# RPI_CM5_PINOUT.net
KiCad netlist of a schematic drawn in Altium Designer
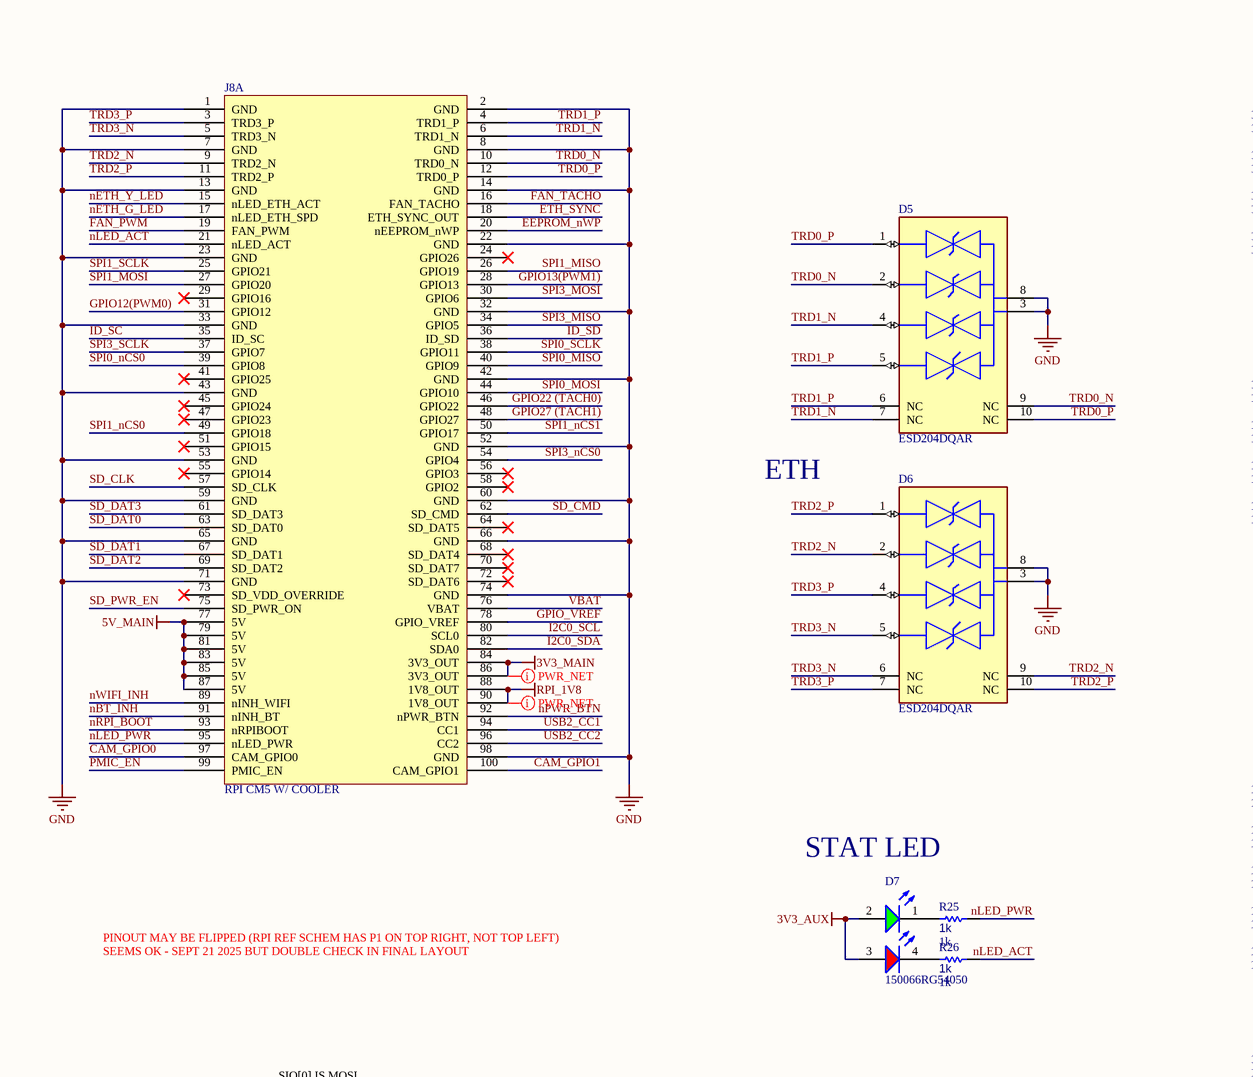
[diagram p0: RPI_CM5_PINOUT.SchDoc, top left]
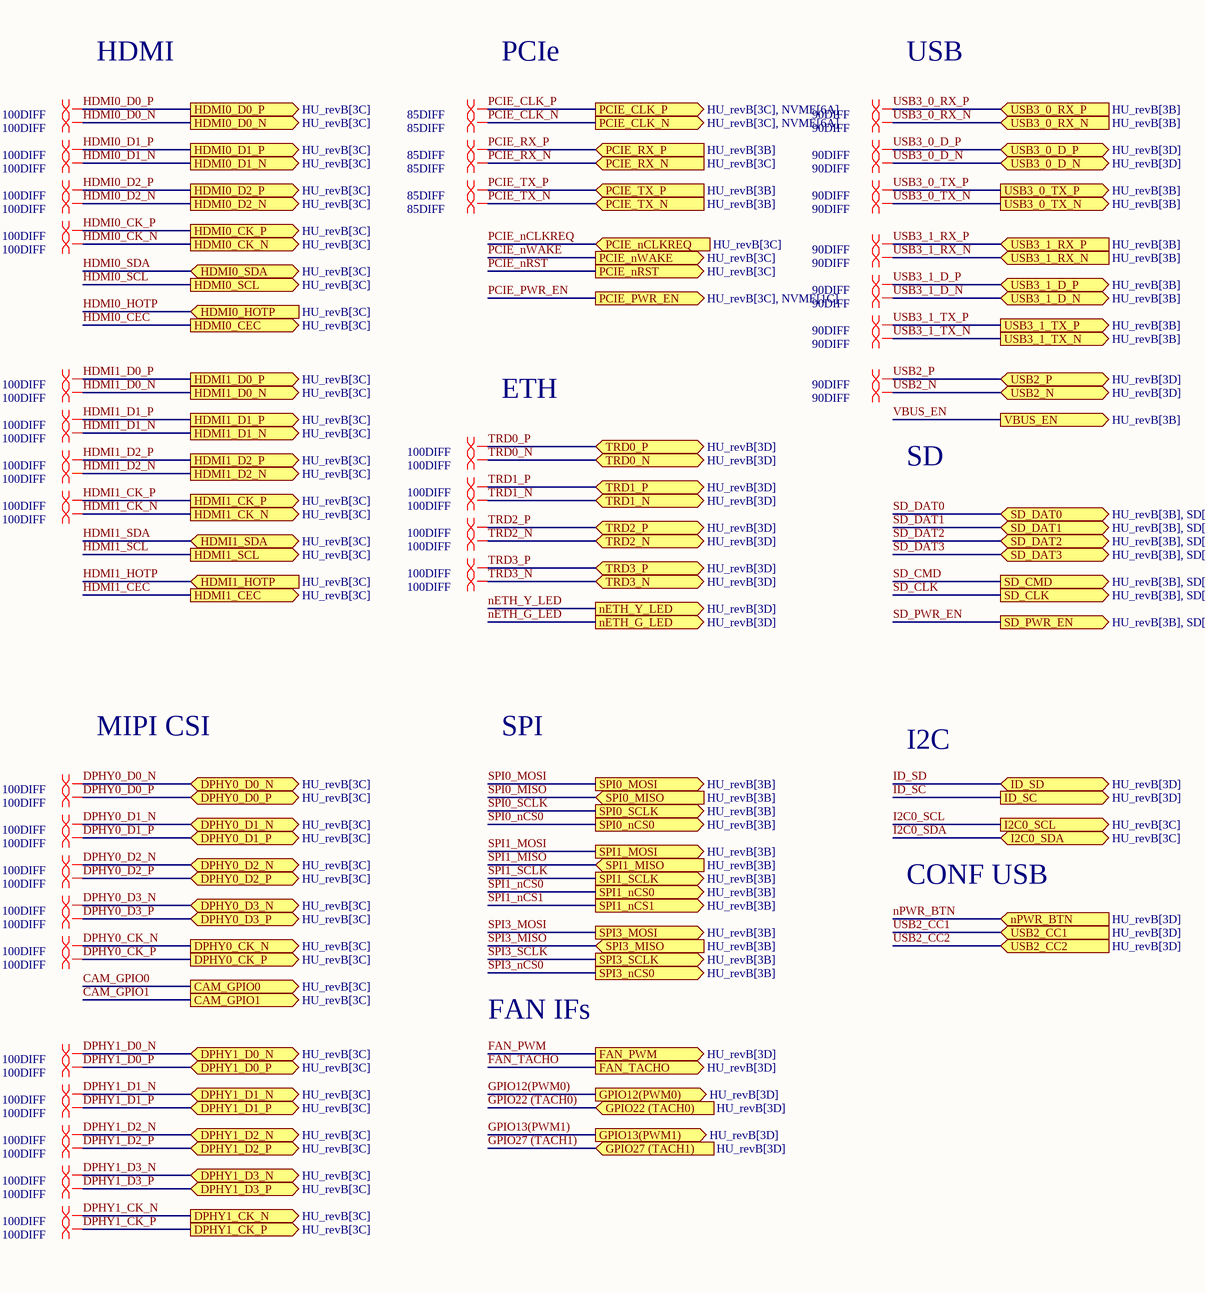
[diagram p1: RPI_CM5_PINOUT.SchDoc, top right]
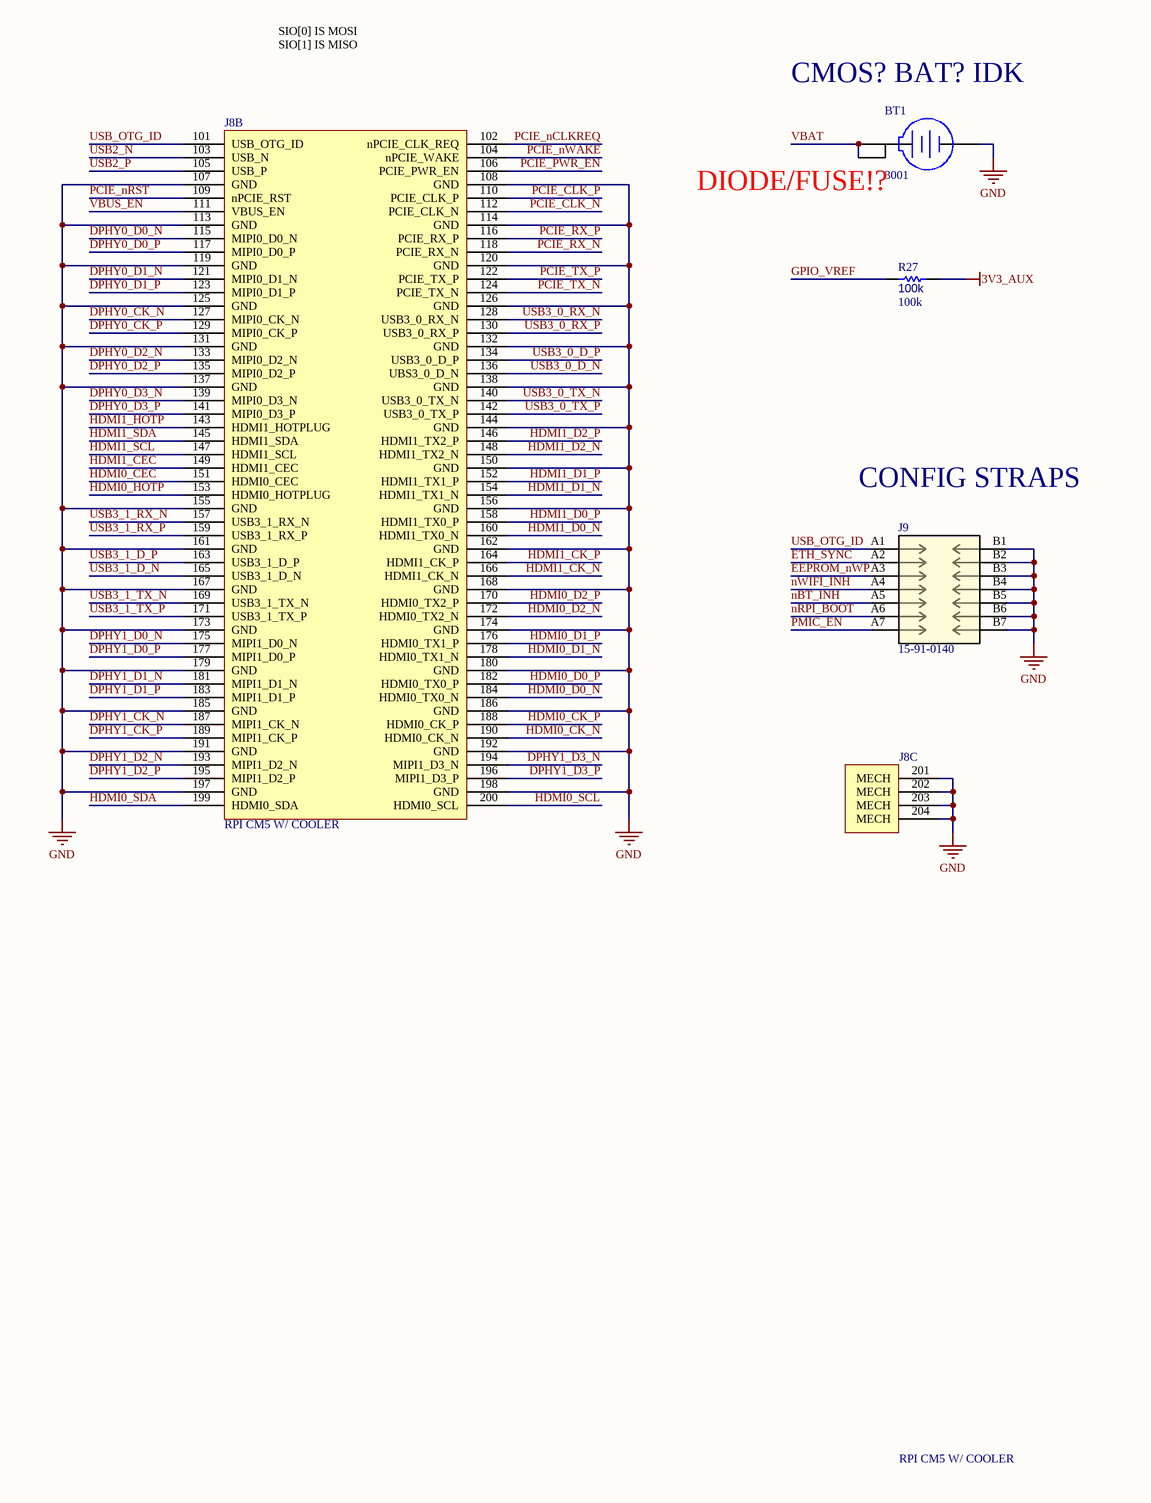
[diagram p2: RPI_CM5_PINOUT.SchDoc, bottom left]
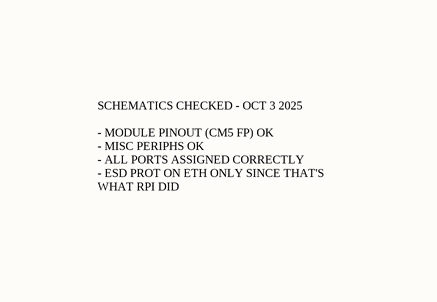
[diagram p3: RPI_CM5_PINOUT.SchDoc, bottom right]

(export (version "E")
  (design (tool "Eeschema 10.0.6"))
  (components
    (comp (ref "BT1")
      (value "3001")
      (footprint "KSTN-3001_V")
      (description "Holder Battery Coin, 12 mm, 2-Pin THD, RoHS")
      (fields (field (name "MANUFACTURER") "Keystone"))
      (libsource (lib "Altium Content Vault") (part "BATTERY-HOLDER-COIN-3"))
    )
    (comp (ref "D5")
      (value "ESD204DQAR")
      (footprint "FP-DQA0010A-MFG")
      (description "4-CHANNEL LOW-CAPACITANCE SURGE")
      (fields
        (field (name "MANUFACTURER") "Texas Instruments")
        (field (name "OCTOPART") "https://octopart.com/esd204dqar-texas+instruments-89917476")
      )
      (libsource (lib "Altium Content Vault") (part "1465e58c1818c7767b55926832f0bf5"))
    )
    (comp (ref "D6")
      (value "ESD204DQAR")
      (footprint "FP-DQA0010A-MFG")
      (description "4-CHANNEL LOW-CAPACITANCE SURGE")
      (fields
        (field (name "MANUFACTURER") "Texas Instruments")
        (field (name "OCTOPART") "https://octopart.com/esd204dqar-texas+instruments-89917476")
      )
      (libsource (lib "Altium Content Vault") (part "1465e58c1818c7767b55926832f0bf5"))
    )
    (comp (ref "D7")
      (value "150066RG54050")
      (footprint "WL-SBCD_0606")
      (description "Led, Red/Grn, 180Mcd/230Mcd, 624Nm/525Nm Rohs Compliant: Yes")
      (fields (field (name "SOURCE") "rgled.SchLib"))
      (libsource (lib "Space Concordia") (part "CMP-004-00034-2"))
    )
    (comp (ref "J8")
      (value "RPI CM5 W/ COOLER")
      (footprint "RPI CM5 W_ COOLER-Footprint-1")
      (description "Mechanical placeholder for RPI CM5 w/ active cooler on it")
      (libsource (lib "Space Concordia") (part "10164227-1001A1RLF"))
    )
    (comp (ref "J9")
      (value "15-91-0140")
      (footprint "15-91-0140-Footprint-1")
      (description "Conn.; Rect./PCB; Header; 14 Circuit; SMT; Dual Row; Vertical; C-Grid Series; Gold Plate")
      (libsource (lib "Space Concordia") (part "15-91-0140"))
    )
    (comp (ref "R25")
      (value "1k")
      (footprint "R0603B")
      (description "Resistor")
      (fields (field (name "ALTIUM_VALUE") "1k"))
      (libsource (lib "Space Concordia") (part "Resistor"))
    )
    (comp (ref "R26")
      (value "1k")
      (footprint "R0603B")
      (description "Resistor")
      (fields (field (name "ALTIUM_VALUE") "1k"))
      (libsource (lib "Space Concordia") (part "Resistor"))
    )
    (comp (ref "R27")
      (value "100k")
      (footprint "R0603B")
      (description "Resistor")
      (fields (field (name "ALTIUM_VALUE") "100k"))
      (libsource (lib "Space Concordia") (part "Resistor"))
    )
  )
  (nets
    (net (code "1") (name "/CAM_GPIO0") (class "Default")
      (node (ref "J8") (pin "97") (pinfunction "CAM_GPIO0_97") (pintype "passive"))
    )
    (net (code "2") (name "/CAM_GPIO1") (class "Default")
      (node (ref "J8") (pin "100") (pinfunction "CAM_GPIO1_100") (pintype "passive"))
    )
    (net (code "3") (name "/DPHY0_CK_N") (class "Default")
      (node (ref "J8") (pin "127") (pinfunction "MIPI0_CK_N_127") (pintype "passive"))
    )
    (net (code "4") (name "/DPHY0_CK_P") (class "Default")
      (node (ref "J8") (pin "129") (pinfunction "MIPI0_CK_P_129") (pintype "passive"))
    )
    (net (code "5") (name "/DPHY0_D0_N") (class "Default")
      (node (ref "J8") (pin "115") (pinfunction "MIPI0_D0_N_115") (pintype "passive"))
    )
    (net (code "6") (name "/DPHY0_D0_P") (class "Default")
      (node (ref "J8") (pin "117") (pinfunction "MIPI0_D0_P_117") (pintype "passive"))
    )
    (net (code "7") (name "/DPHY0_D1_N") (class "Default")
      (node (ref "J8") (pin "121") (pinfunction "MIPI0_D1_N_121") (pintype "passive"))
    )
    (net (code "8") (name "/DPHY0_D1_P") (class "Default")
      (node (ref "J8") (pin "123") (pinfunction "MIPI0_D1_P_123") (pintype "passive"))
    )
    (net (code "9") (name "/DPHY0_D2_N") (class "Default")
      (node (ref "J8") (pin "133") (pinfunction "MIPI0_D2_N_133") (pintype "passive"))
    )
    (net (code "10") (name "/DPHY0_D2_P") (class "Default")
      (node (ref "J8") (pin "135") (pinfunction "MIPI0_D2_P_135") (pintype "passive"))
    )
    (net (code "11") (name "/DPHY0_D3_N") (class "Default")
      (node (ref "J8") (pin "139") (pinfunction "MIPI0_D3_N_139") (pintype "passive"))
    )
    (net (code "12") (name "/DPHY0_D3_P") (class "Default")
      (node (ref "J8") (pin "141") (pinfunction "MIPI0_D3_P_141") (pintype "passive"))
    )
    (net (code "13") (name "/DPHY1_CK_N") (class "Default")
      (node (ref "J8") (pin "187") (pinfunction "MIPI1_CK_N_187") (pintype "passive"))
    )
    (net (code "14") (name "/DPHY1_CK_P") (class "Default")
      (node (ref "J8") (pin "189") (pinfunction "MIPI1_CK_P_189") (pintype "passive"))
    )
    (net (code "15") (name "/DPHY1_D0_N") (class "Default")
      (node (ref "J8") (pin "175") (pinfunction "MIPI1_D0_N_175") (pintype "passive"))
    )
    (net (code "16") (name "/DPHY1_D0_P") (class "Default")
      (node (ref "J8") (pin "177") (pinfunction "MIPI1_D0_P_177") (pintype "passive"))
    )
    (net (code "17") (name "/DPHY1_D1_N") (class "Default")
      (node (ref "J8") (pin "181") (pinfunction "MIPI1_D1_N_181") (pintype "passive"))
    )
    (net (code "18") (name "/DPHY1_D1_P") (class "Default")
      (node (ref "J8") (pin "183") (pinfunction "MIPI1_D1_P_183") (pintype "passive"))
    )
    (net (code "19") (name "/DPHY1_D2_N") (class "Default")
      (node (ref "J8") (pin "193") (pinfunction "MIPI1_D2_N_193") (pintype "passive"))
    )
    (net (code "20") (name "/DPHY1_D2_P") (class "Default")
      (node (ref "J8") (pin "195") (pinfunction "MIPI1_D2_P_195") (pintype "passive"))
    )
    (net (code "21") (name "/DPHY1_D3_N") (class "Default")
      (node (ref "J8") (pin "194") (pinfunction "MIPI1_D3_N_194") (pintype "passive"))
    )
    (net (code "22") (name "/DPHY1_D3_P") (class "Default")
      (node (ref "J8") (pin "196") (pinfunction "MIPI1_D3_P_196") (pintype "passive"))
    )
    (net (code "23") (name "/EEPROM_nWP") (class "Default")
      (node (ref "J8") (pin "20") (pinfunction "nEEPROM_nWP_20") (pintype "passive"))
      (node (ref "J9") (pin "A3") (pinfunction "A3_A3") (pintype "passive"))
    )
    (net (code "24") (name "/ETH_SYNC") (class "Default")
      (node (ref "J8") (pin "18") (pinfunction "ETH_SYNC_OUT_18") (pintype "passive"))
      (node (ref "J9") (pin "A2") (pinfunction "A2_A2") (pintype "passive"))
    )
    (net (code "25") (name "/FAN_PWM") (class "Default")
      (node (ref "J8") (pin "19") (pinfunction "FAN_PWM_19") (pintype "passive"))
    )
    (net (code "26") (name "/FAN_TACHO") (class "Default")
      (node (ref "J8") (pin "16") (pinfunction "FAN_TACHO_16") (pintype "passive"))
    )
    (net (code "27") (name "/GPIO12(PWM0)") (class "Default")
      (node (ref "J8") (pin "31") (pinfunction "GPIO12_31") (pintype "passive"))
    )
    (net (code "28") (name "/GPIO13(PWM1)") (class "Default")
      (node (ref "J8") (pin "28") (pinfunction "GPIO13_28") (pintype "passive"))
    )
    (net (code "29") (name "/GPIO22 (TACH0)") (class "Default")
      (node (ref "J8") (pin "46") (pinfunction "GPIO22_46") (pintype "passive"))
    )
    (net (code "30") (name "/GPIO27 (TACH1)") (class "Default")
      (node (ref "J8") (pin "48") (pinfunction "GPIO27_48") (pintype "passive"))
    )
    (net (code "31") (name "/GPIO_VREF") (class "Default")
      (node (ref "J8") (pin "78") (pinfunction "GPIO_VREF_78") (pintype "passive"))
      (node (ref "R27") (pin "1") (pinfunction "1_1") (pintype "passive"))
    )
    (net (code "32") (name "/HDMI0_CEC") (class "Default")
      (node (ref "J8") (pin "151") (pinfunction "HDMI0_CEC_151") (pintype "passive"))
    )
    (net (code "33") (name "/HDMI0_CK_N") (class "Default")
      (node (ref "J8") (pin "190") (pinfunction "HDMI0_CK_N_190") (pintype "passive"))
    )
    (net (code "34") (name "/HDMI0_CK_P") (class "Default")
      (node (ref "J8") (pin "188") (pinfunction "HDMI0_CK_P_188") (pintype "passive"))
    )
    (net (code "35") (name "/HDMI0_D0_N") (class "Default")
      (node (ref "J8") (pin "184") (pinfunction "HDMI0_TX0_N_184") (pintype "passive"))
    )
    (net (code "36") (name "/HDMI0_D0_P") (class "Default")
      (node (ref "J8") (pin "182") (pinfunction "HDMI0_TX0_P_182") (pintype "passive"))
    )
    (net (code "37") (name "/HDMI0_D1_N") (class "Default")
      (node (ref "J8") (pin "178") (pinfunction "HDMI0_TX1_N_178") (pintype "passive"))
    )
    (net (code "38") (name "/HDMI0_D1_P") (class "Default")
      (node (ref "J8") (pin "176") (pinfunction "HDMI0_TX1_P_176") (pintype "passive"))
    )
    (net (code "39") (name "/HDMI0_D2_N") (class "Default")
      (node (ref "J8") (pin "172") (pinfunction "HDMI0_TX2_N_172") (pintype "passive"))
    )
    (net (code "40") (name "/HDMI0_D2_P") (class "Default")
      (node (ref "J8") (pin "170") (pinfunction "HDMI0_TX2_P_170") (pintype "passive"))
    )
    (net (code "41") (name "/HDMI0_HOTP") (class "Default")
      (node (ref "J8") (pin "153") (pinfunction "HDMI0_HOTPLUG_153") (pintype "passive"))
    )
    (net (code "42") (name "/HDMI0_SCL") (class "Default")
      (node (ref "J8") (pin "200") (pinfunction "HDMI0_SCL_200") (pintype "passive"))
    )
    (net (code "43") (name "/HDMI0_SDA") (class "Default")
      (node (ref "J8") (pin "199") (pinfunction "HDMI0_SDA_199") (pintype "passive"))
    )
    (net (code "44") (name "/HDMI1_CEC") (class "Default")
      (node (ref "J8") (pin "149") (pinfunction "HDMI1_CEC_149") (pintype "passive"))
    )
    (net (code "45") (name "/HDMI1_CK_N") (class "Default")
      (node (ref "J8") (pin "166") (pinfunction "HDMI1_CK_N_166") (pintype "passive"))
    )
    (net (code "46") (name "/HDMI1_CK_P") (class "Default")
      (node (ref "J8") (pin "164") (pinfunction "HDMI1_CK_P_164") (pintype "passive"))
    )
    (net (code "47") (name "/HDMI1_D0_N") (class "Default")
      (node (ref "J8") (pin "160") (pinfunction "HDMI1_TX0_N_160") (pintype "passive"))
    )
    (net (code "48") (name "/HDMI1_D0_P") (class "Default")
      (node (ref "J8") (pin "158") (pinfunction "HDMI1_TX0_P_158") (pintype "passive"))
    )
    (net (code "49") (name "/HDMI1_D1_N") (class "Default")
      (node (ref "J8") (pin "154") (pinfunction "HDMI1_TX1_N_154") (pintype "passive"))
    )
    (net (code "50") (name "/HDMI1_D1_P") (class "Default")
      (node (ref "J8") (pin "152") (pinfunction "HDMI1_TX1_P_152") (pintype "passive"))
    )
    (net (code "51") (name "/HDMI1_D2_N") (class "Default")
      (node (ref "J8") (pin "148") (pinfunction "HDMI1_TX2_N_148") (pintype "passive"))
    )
    (net (code "52") (name "/HDMI1_D2_P") (class "Default")
      (node (ref "J8") (pin "146") (pinfunction "HDMI1_TX2_P_146") (pintype "passive"))
    )
    (net (code "53") (name "/HDMI1_HOTP") (class "Default")
      (node (ref "J8") (pin "143") (pinfunction "HDMI1_HOTPLUG_143") (pintype "passive"))
    )
    (net (code "54") (name "/HDMI1_SCL") (class "Default")
      (node (ref "J8") (pin "147") (pinfunction "HDMI1_SCL_147") (pintype "passive"))
    )
    (net (code "55") (name "/HDMI1_SDA") (class "Default")
      (node (ref "J8") (pin "145") (pinfunction "HDMI1_SDA_145") (pintype "passive"))
    )
    (net (code "56") (name "/I2C0_SCL") (class "Default")
      (node (ref "J8") (pin "80") (pinfunction "SCL0_80") (pintype "passive"))
    )
    (net (code "57") (name "/I2C0_SDA") (class "Default")
      (node (ref "J8") (pin "82") (pinfunction "SDA0_82") (pintype "passive"))
    )
    (net (code "58") (name "/ID_SC") (class "Default")
      (node (ref "J8") (pin "35") (pinfunction "ID_SC_35") (pintype "passive"))
    )
    (net (code "59") (name "/ID_SD") (class "Default")
      (node (ref "J8") (pin "36") (pinfunction "ID_SD_36") (pintype "passive"))
    )
    (net (code "60") (name "/PCIE_CLK_N") (class "Default")
      (node (ref "J8") (pin "112") (pinfunction "PCIE_CLK_N_112") (pintype "passive"))
    )
    (net (code "61") (name "/PCIE_CLK_P") (class "Default")
      (node (ref "J8") (pin "110") (pinfunction "PCIE_CLK_P_110") (pintype "passive"))
    )
    (net (code "62") (name "/PCIE_PWR_EN") (class "Default")
      (node (ref "J8") (pin "106") (pinfunction "PCIE_PWR_EN_106") (pintype "passive"))
    )
    (net (code "63") (name "/PCIE_RX_N") (class "Default")
      (node (ref "J8") (pin "118") (pinfunction "PCIE_RX_N_118") (pintype "passive"))
    )
    (net (code "64") (name "/PCIE_RX_P") (class "Default")
      (node (ref "J8") (pin "116") (pinfunction "PCIE_RX_P_116") (pintype "passive"))
    )
    (net (code "65") (name "/PCIE_TX_N") (class "Default")
      (node (ref "J8") (pin "124") (pinfunction "PCIE_TX_N_124") (pintype "passive"))
    )
    (net (code "66") (name "/PCIE_TX_P") (class "Default")
      (node (ref "J8") (pin "122") (pinfunction "PCIE_TX_P_122") (pintype "passive"))
    )
    (net (code "67") (name "/PCIE_nCLKREQ") (class "Default")
      (node (ref "J8") (pin "102") (pinfunction "nPCIE_CLK_REQ_102") (pintype "passive"))
    )
    (net (code "68") (name "/PCIE_nRST") (class "Default")
      (node (ref "J8") (pin "109") (pinfunction "nPCIE_RST_109") (pintype "passive"))
    )
    (net (code "69") (name "/PCIE_nWAKE") (class "Default")
      (node (ref "J8") (pin "104") (pinfunction "nPCIE_WAKE_104") (pintype "passive"))
    )
    (net (code "70") (name "/PMIC_EN") (class "Default")
      (node (ref "J8") (pin "99") (pinfunction "PMIC_EN_99") (pintype "passive"))
      (node (ref "J9") (pin "A7") (pinfunction "A7_A7") (pintype "passive"))
    )
    (net (code "71") (name "/SD_CLK") (class "Default")
      (node (ref "J8") (pin "57") (pinfunction "SD_CLK_57") (pintype "passive"))
    )
    (net (code "72") (name "/SD_CMD") (class "Default")
      (node (ref "J8") (pin "62") (pinfunction "SD_CMD_62") (pintype "passive"))
    )
    (net (code "73") (name "/SD_DAT0") (class "Default")
      (node (ref "J8") (pin "63") (pinfunction "SD_DAT0_63") (pintype "passive"))
    )
    (net (code "74") (name "/SD_DAT1") (class "Default")
      (node (ref "J8") (pin "67") (pinfunction "SD_DAT1_67") (pintype "passive"))
    )
    (net (code "75") (name "/SD_DAT2") (class "Default")
      (node (ref "J8") (pin "69") (pinfunction "SD_DAT2_69") (pintype "passive"))
    )
    (net (code "76") (name "/SD_DAT3") (class "Default")
      (node (ref "J8") (pin "61") (pinfunction "SD_DAT3_61") (pintype "passive"))
    )
    (net (code "77") (name "/SD_PWR_EN") (class "Default")
      (node (ref "J8") (pin "75") (pinfunction "SD_PWR_ON_75") (pintype "passive"))
    )
    (net (code "78") (name "/SPI0_MISO") (class "Default")
      (node (ref "J8") (pin "40") (pinfunction "GPIO9_40") (pintype "passive"))
    )
    (net (code "79") (name "/SPI0_MOSI") (class "Default")
      (node (ref "J8") (pin "44") (pinfunction "GPIO10_44") (pintype "passive"))
    )
    (net (code "80") (name "/SPI0_SCLK") (class "Default")
      (node (ref "J8") (pin "38") (pinfunction "GPIO11_38") (pintype "passive"))
    )
    (net (code "81") (name "/SPI0_nCS0") (class "Default")
      (node (ref "J8") (pin "39") (pinfunction "GPIO8_39") (pintype "passive"))
    )
    (net (code "82") (name "/SPI1_MISO") (class "Default")
      (node (ref "J8") (pin "26") (pinfunction "GPIO19_26") (pintype "passive"))
    )
    (net (code "83") (name "/SPI1_MOSI") (class "Default")
      (node (ref "J8") (pin "27") (pinfunction "GPIO20_27") (pintype "passive"))
    )
    (net (code "84") (name "/SPI1_SCLK") (class "Default")
      (node (ref "J8") (pin "25") (pinfunction "GPIO21_25") (pintype "passive"))
    )
    (net (code "85") (name "/SPI1_nCS0") (class "Default")
      (node (ref "J8") (pin "49") (pinfunction "GPIO18_49") (pintype "passive"))
    )
    (net (code "86") (name "/SPI1_nCS1") (class "Default")
      (node (ref "J8") (pin "50") (pinfunction "GPIO17_50") (pintype "passive"))
    )
    (net (code "87") (name "/SPI3_MISO") (class "Default")
      (node (ref "J8") (pin "34") (pinfunction "GPIO5_34") (pintype "passive"))
    )
    (net (code "88") (name "/SPI3_MOSI") (class "Default")
      (node (ref "J8") (pin "30") (pinfunction "GPIO6_30") (pintype "passive"))
    )
    (net (code "89") (name "/SPI3_SCLK") (class "Default")
      (node (ref "J8") (pin "37") (pinfunction "GPIO7_37") (pintype "passive"))
    )
    (net (code "90") (name "/SPI3_nCS0") (class "Default")
      (node (ref "J8") (pin "54") (pinfunction "GPIO4_54") (pintype "passive"))
    )
    (net (code "91") (name "/TRD0_N") (class "Default")
      (node (ref "D5") (pin "2") (pinfunction "IO2_2") (pintype "bidirectional"))
      (node (ref "D5") (pin "9") (pinfunction "NC_9") (pintype "passive"))
      (node (ref "J8") (pin "10") (pinfunction "TRD0_N_10") (pintype "passive"))
    )
    (net (code "92") (name "/TRD0_P") (class "Default")
      (node (ref "D5") (pin "1") (pinfunction "IO1_1") (pintype "bidirectional"))
      (node (ref "D5") (pin "10") (pinfunction "NC_10") (pintype "passive"))
      (node (ref "J8") (pin "12") (pinfunction "TRD0_P_12") (pintype "passive"))
    )
    (net (code "93") (name "/TRD1_N") (class "Default")
      (node (ref "D5") (pin "4") (pinfunction "IO3_4") (pintype "bidirectional"))
      (node (ref "D5") (pin "7") (pinfunction "NC_7") (pintype "passive"))
      (node (ref "J8") (pin "6") (pinfunction "TRD1_N_6") (pintype "passive"))
    )
    (net (code "94") (name "/TRD1_P") (class "Default")
      (node (ref "D5") (pin "5") (pinfunction "IO4_5") (pintype "bidirectional"))
      (node (ref "D5") (pin "6") (pinfunction "NC_6") (pintype "passive"))
      (node (ref "J8") (pin "4") (pinfunction "TRD1_P_4") (pintype "passive"))
    )
    (net (code "95") (name "/TRD2_N") (class "Default")
      (node (ref "D6") (pin "2") (pinfunction "IO2_2") (pintype "bidirectional"))
      (node (ref "D6") (pin "9") (pinfunction "NC_9") (pintype "passive"))
      (node (ref "J8") (pin "9") (pinfunction "TRD2_N_9") (pintype "passive"))
    )
    (net (code "96") (name "/TRD2_P") (class "Default")
      (node (ref "D6") (pin "1") (pinfunction "IO1_1") (pintype "bidirectional"))
      (node (ref "D6") (pin "10") (pinfunction "NC_10") (pintype "passive"))
      (node (ref "J8") (pin "11") (pinfunction "TRD2_P_11") (pintype "passive"))
    )
    (net (code "97") (name "/TRD3_N") (class "Default")
      (node (ref "D6") (pin "5") (pinfunction "IO4_5") (pintype "bidirectional"))
      (node (ref "D6") (pin "6") (pinfunction "NC_6") (pintype "passive"))
      (node (ref "J8") (pin "5") (pinfunction "TRD3_N_5") (pintype "passive"))
    )
    (net (code "98") (name "/TRD3_P") (class "Default")
      (node (ref "D6") (pin "4") (pinfunction "IO3_4") (pintype "bidirectional"))
      (node (ref "D6") (pin "7") (pinfunction "NC_7") (pintype "passive"))
      (node (ref "J8") (pin "3") (pinfunction "TRD3_P_3") (pintype "passive"))
    )
    (net (code "99") (name "/USB2_CC1") (class "Default")
      (node (ref "J8") (pin "94") (pinfunction "CC1_94") (pintype "passive"))
    )
    (net (code "100") (name "/USB2_CC2") (class "Default")
      (node (ref "J8") (pin "96") (pinfunction "CC2_96") (pintype "passive"))
    )
    (net (code "101") (name "/USB2_N") (class "Default")
      (node (ref "J8") (pin "103") (pinfunction "USB_N_103") (pintype "passive"))
    )
    (net (code "102") (name "/USB2_P") (class "Default")
      (node (ref "J8") (pin "105") (pinfunction "USB_P_105") (pintype "passive"))
    )
    (net (code "103") (name "/USB3_0_D_N") (class "Default")
      (node (ref "J8") (pin "136") (pinfunction "UBS3_0_D_N_136") (pintype "passive"))
    )
    (net (code "104") (name "/USB3_0_D_P") (class "Default")
      (node (ref "J8") (pin "134") (pinfunction "USB3_0_D_P_134") (pintype "passive"))
    )
    (net (code "105") (name "/USB3_0_RX_N") (class "Default")
      (node (ref "J8") (pin "128") (pinfunction "USB3_0_RX_N_128") (pintype "passive"))
    )
    (net (code "106") (name "/USB3_0_RX_P") (class "Default")
      (node (ref "J8") (pin "130") (pinfunction "USB3_0_RX_P_130") (pintype "passive"))
    )
    (net (code "107") (name "/USB3_0_TX_N") (class "Default")
      (node (ref "J8") (pin "140") (pinfunction "USB3_0_TX_N_140") (pintype "passive"))
    )
    (net (code "108") (name "/USB3_0_TX_P") (class "Default")
      (node (ref "J8") (pin "142") (pinfunction "USB3_0_TX_P_142") (pintype "passive"))
    )
    (net (code "109") (name "/USB3_1_D_N") (class "Default")
      (node (ref "J8") (pin "165") (pinfunction "USB3_1_D_N_165") (pintype "passive"))
    )
    (net (code "110") (name "/USB3_1_D_P") (class "Default")
      (node (ref "J8") (pin "163") (pinfunction "USB3_1_D_P_163") (pintype "passive"))
    )
    (net (code "111") (name "/USB3_1_RX_N") (class "Default")
      (node (ref "J8") (pin "157") (pinfunction "USB3_1_RX_N_157") (pintype "passive"))
    )
    (net (code "112") (name "/USB3_1_RX_P") (class "Default")
      (node (ref "J8") (pin "159") (pinfunction "USB3_1_RX_P_159") (pintype "passive"))
    )
    (net (code "113") (name "/USB3_1_TX_N") (class "Default")
      (node (ref "J8") (pin "169") (pinfunction "USB3_1_TX_N_169") (pintype "passive"))
    )
    (net (code "114") (name "/USB3_1_TX_P") (class "Default")
      (node (ref "J8") (pin "171") (pinfunction "USB3_1_TX_P_171") (pintype "passive"))
    )
    (net (code "115") (name "/USB_OTG_ID") (class "Default")
      (node (ref "J8") (pin "101") (pinfunction "USB_OTG_ID_101") (pintype "passive"))
      (node (ref "J9") (pin "A1") (pinfunction "A1_A1") (pintype "passive"))
    )
    (net (code "116") (name "/VBAT") (class "Default")
      (node (ref "BT1") (pin "1") (pinfunction "+_1") (pintype "passive"))
      (node (ref "BT1") (pin "2") (pinfunction "+_2") (pintype "passive"))
      (node (ref "J8") (pin "76") (pinfunction "VBAT_76") (pintype "passive"))
    )
    (net (code "117") (name "/VBUS_EN") (class "Default")
      (node (ref "J8") (pin "111") (pinfunction "VBUS_EN_111") (pintype "passive"))
    )
    (net (code "118") (name "/nBT_INH") (class "Default")
      (node (ref "J8") (pin "91") (pinfunction "nINH_BT_91") (pintype "passive"))
      (node (ref "J9") (pin "A5") (pinfunction "A5_A5") (pintype "passive"))
    )
    (net (code "119") (name "/nETH_G_LED") (class "Default")
      (node (ref "J8") (pin "17") (pinfunction "nLED_ETH_SPD_17") (pintype "passive"))
    )
    (net (code "120") (name "/nETH_Y_LED") (class "Default")
      (node (ref "J8") (pin "15") (pinfunction "nLED_ETH_ACT_15") (pintype "passive"))
    )
    (net (code "121") (name "/nLED_ACT") (class "Default")
      (node (ref "J8") (pin "21") (pinfunction "nLED_ACT_21") (pintype "passive"))
      (node (ref "R26") (pin "2") (pinfunction "2_2") (pintype "passive"))
    )
    (net (code "122") (name "/nLED_PWR") (class "Default")
      (node (ref "J8") (pin "95") (pinfunction "nLED_PWR_95") (pintype "passive"))
      (node (ref "R25") (pin "2") (pinfunction "2_2") (pintype "passive"))
    )
    (net (code "123") (name "/nPWR_BTN") (class "Default")
      (node (ref "J8") (pin "92") (pinfunction "nPWR_BTN_92") (pintype "passive"))
    )
    (net (code "124") (name "/nRPI_BOOT") (class "Default")
      (node (ref "J8") (pin "93") (pinfunction "nRPIBOOT_93") (pintype "passive"))
      (node (ref "J9") (pin "A6") (pinfunction "A6_A6") (pintype "passive"))
    )
    (net (code "125") (name "/nWIFI_INH") (class "Default")
      (node (ref "J8") (pin "89") (pinfunction "nINH_WIFI_89") (pintype "passive"))
      (node (ref "J9") (pin "A4") (pinfunction "A4_A4") (pintype "passive"))
    )
    (net (code "126") (name "3V3_AUX") (class "Default")
      (node (ref "D7") (pin "2") (pinfunction "A_2") (pintype "passive"))
      (node (ref "D7") (pin "3") (pinfunction "A_3") (pintype "passive"))
      (node (ref "R27") (pin "2") (pinfunction "2_2") (pintype "passive"))
    )
    (net (code "127") (name "3V3_MAIN") (class "Default")
      (node (ref "J8") (pin "84") (pinfunction "3V3_OUT_84") (pintype "passive"))
      (node (ref "J8") (pin "86") (pinfunction "3V3_OUT_86") (pintype "passive"))
    )
    (net (code "128") (name "5V_MAIN") (class "Default")
      (node (ref "J8") (pin "77") (pinfunction "5V_77") (pintype "passive"))
      (node (ref "J8") (pin "79") (pinfunction "5V_79") (pintype "passive"))
      (node (ref "J8") (pin "81") (pinfunction "5V_81") (pintype "passive"))
      (node (ref "J8") (pin "83") (pinfunction "5V_83") (pintype "passive"))
      (node (ref "J8") (pin "85") (pinfunction "5V_85") (pintype "passive"))
      (node (ref "J8") (pin "87") (pinfunction "5V_87") (pintype "passive"))
    )
    (net (code "129") (name "GND") (class "Default")
      (node (ref "BT1") (pin "3") (pinfunction "-_3") (pintype "passive"))
      (node (ref "D5") (pin "3") (pinfunction "GND_3") (pintype "power_in"))
      (node (ref "D5") (pin "8") (pinfunction "GND_8") (pintype "power_in"))
      (node (ref "D6") (pin "3") (pinfunction "GND_3") (pintype "power_in"))
      (node (ref "D6") (pin "8") (pinfunction "GND_8") (pintype "power_in"))
      (node (ref "J8") (pin "1") (pinfunction "GND_1") (pintype "passive"))
      (node (ref "J8") (pin "107") (pinfunction "GND_107") (pintype "passive"))
      (node (ref "J8") (pin "108") (pinfunction "GND_108") (pintype "passive"))
      (node (ref "J8") (pin "113") (pinfunction "GND_113") (pintype "passive"))
      (node (ref "J8") (pin "114") (pinfunction "GND_114") (pintype "passive"))
      (node (ref "J8") (pin "119") (pinfunction "GND_119") (pintype "passive"))
      (node (ref "J8") (pin "120") (pinfunction "GND_120") (pintype "passive"))
      (node (ref "J8") (pin "125") (pinfunction "GND_125") (pintype "passive"))
      (node (ref "J8") (pin "126") (pinfunction "GND_126") (pintype "passive"))
      (node (ref "J8") (pin "13") (pinfunction "GND_13") (pintype "passive"))
      (node (ref "J8") (pin "131") (pinfunction "GND_131") (pintype "passive"))
      (node (ref "J8") (pin "132") (pinfunction "GND_132") (pintype "passive"))
      (node (ref "J8") (pin "137") (pinfunction "GND_137") (pintype "passive"))
      (node (ref "J8") (pin "138") (pinfunction "GND_138") (pintype "passive"))
      (node (ref "J8") (pin "14") (pinfunction "GND_14") (pintype "passive"))
      (node (ref "J8") (pin "144") (pinfunction "GND_144") (pintype "passive"))
      (node (ref "J8") (pin "150") (pinfunction "GND_150") (pintype "passive"))
      (node (ref "J8") (pin "155") (pinfunction "GND_155") (pintype "passive"))
      (node (ref "J8") (pin "156") (pinfunction "GND_156") (pintype "passive"))
      (node (ref "J8") (pin "161") (pinfunction "GND_161") (pintype "passive"))
      (node (ref "J8") (pin "162") (pinfunction "GND_162") (pintype "passive"))
      (node (ref "J8") (pin "167") (pinfunction "GND_167") (pintype "passive"))
      (node (ref "J8") (pin "168") (pinfunction "GND_168") (pintype "passive"))
      (node (ref "J8") (pin "173") (pinfunction "GND_173") (pintype "passive"))
      (node (ref "J8") (pin "174") (pinfunction "GND_174") (pintype "passive"))
      (node (ref "J8") (pin "179") (pinfunction "GND_179") (pintype "passive"))
      (node (ref "J8") (pin "180") (pinfunction "GND_180") (pintype "passive"))
      (node (ref "J8") (pin "185") (pinfunction "GND_185") (pintype "passive"))
      (node (ref "J8") (pin "186") (pinfunction "GND_186") (pintype "passive"))
      (node (ref "J8") (pin "191") (pinfunction "GND_191") (pintype "passive"))
      (node (ref "J8") (pin "192") (pinfunction "GND_192") (pintype "passive"))
      (node (ref "J8") (pin "197") (pinfunction "GND_197") (pintype "passive"))
      (node (ref "J8") (pin "198") (pinfunction "GND_198") (pintype "passive"))
      (node (ref "J8") (pin "2") (pinfunction "GND_2") (pintype "passive"))
      (node (ref "J8") (pin "201") (pinfunction "MECH_201") (pintype "passive"))
      (node (ref "J8") (pin "202") (pinfunction "MECH_202") (pintype "passive"))
      (node (ref "J8") (pin "203") (pinfunction "MECH_203") (pintype "passive"))
      (node (ref "J8") (pin "204") (pinfunction "MECH_204") (pintype "passive"))
      (node (ref "J8") (pin "22") (pinfunction "GND_22") (pintype "passive"))
      (node (ref "J8") (pin "23") (pinfunction "GND_23") (pintype "passive"))
      (node (ref "J8") (pin "32") (pinfunction "GND_32") (pintype "passive"))
      (node (ref "J8") (pin "33") (pinfunction "GND_33") (pintype "passive"))
      (node (ref "J8") (pin "42") (pinfunction "GND_42") (pintype "passive"))
      (node (ref "J8") (pin "43") (pinfunction "GND_43") (pintype "passive"))
      (node (ref "J8") (pin "52") (pinfunction "GND_52") (pintype "passive"))
      (node (ref "J8") (pin "53") (pinfunction "GND_53") (pintype "passive"))
      (node (ref "J8") (pin "59") (pinfunction "GND_59") (pintype "passive"))
      (node (ref "J8") (pin "60") (pinfunction "GND_60") (pintype "passive"))
      (node (ref "J8") (pin "65") (pinfunction "GND_65") (pintype "passive"))
      (node (ref "J8") (pin "66") (pinfunction "GND_66") (pintype "passive"))
      (node (ref "J8") (pin "7") (pinfunction "GND_7") (pintype "passive"))
      (node (ref "J8") (pin "71") (pinfunction "GND_71") (pintype "passive"))
      (node (ref "J8") (pin "74") (pinfunction "GND_74") (pintype "passive"))
      (node (ref "J8") (pin "8") (pinfunction "GND_8") (pintype "passive"))
      (node (ref "J8") (pin "98") (pinfunction "GND_98") (pintype "passive"))
      (node (ref "J9") (pin "B1") (pinfunction "B1_B1") (pintype "passive"))
      (node (ref "J9") (pin "B2") (pinfunction "B2_B2") (pintype "passive"))
      (node (ref "J9") (pin "B3") (pinfunction "B3_B3") (pintype "passive"))
      (node (ref "J9") (pin "B4") (pinfunction "B4_B4") (pintype "passive"))
      (node (ref "J9") (pin "B5") (pinfunction "B5_B5") (pintype "passive"))
      (node (ref "J9") (pin "B6") (pinfunction "B6_B6") (pintype "passive"))
      (node (ref "J9") (pin "B7") (pinfunction "B7_B7") (pintype "passive"))
    )
    (net (code "130") (name "Net-(D7-K-Pad1)") (class "Default")
      (node (ref "D7") (pin "1") (pinfunction "K_1") (pintype "passive"))
      (node (ref "R25") (pin "1") (pinfunction "1_1") (pintype "passive"))
    )
    (net (code "131") (name "Net-(D7-K-Pad4)") (class "Default")
      (node (ref "D7") (pin "4") (pinfunction "K_4") (pintype "passive"))
      (node (ref "R26") (pin "1") (pinfunction "1_1") (pintype "passive"))
    )
    (net (code "132") (name "RPI_1V8") (class "Default")
      (node (ref "J8") (pin "88") (pinfunction "1V8_OUT_88") (pintype "passive"))
      (node (ref "J8") (pin "90") (pinfunction "1V8_OUT_90") (pintype "passive"))
    )
    (net (code "133") (name "unconnected-(J8A-GPIO2-Pad58)") (class "Default")
      (node (ref "J8") (pin "58") (pinfunction "GPIO2_58") (pintype "passive+no_connect"))
    )
    (net (code "134") (name "unconnected-(J8A-GPIO3-Pad56)") (class "Default")
      (node (ref "J8") (pin "56") (pinfunction "GPIO3_56") (pintype "passive+no_connect"))
    )
    (net (code "135") (name "unconnected-(J8A-GPIO14-Pad55)") (class "Default")
      (node (ref "J8") (pin "55") (pinfunction "GPIO14_55") (pintype "passive+no_connect"))
    )
    (net (code "136") (name "unconnected-(J8A-GPIO15-Pad51)") (class "Default")
      (node (ref "J8") (pin "51") (pinfunction "GPIO15_51") (pintype "passive+no_connect"))
    )
    (net (code "137") (name "unconnected-(J8A-GPIO16-Pad29)") (class "Default")
      (node (ref "J8") (pin "29") (pinfunction "GPIO16_29") (pintype "passive+no_connect"))
    )
    (net (code "138") (name "unconnected-(J8A-GPIO23-Pad47)") (class "Default")
      (node (ref "J8") (pin "47") (pinfunction "GPIO23_47") (pintype "passive+no_connect"))
    )
    (net (code "139") (name "unconnected-(J8A-GPIO24-Pad45)") (class "Default")
      (node (ref "J8") (pin "45") (pinfunction "GPIO24_45") (pintype "passive+no_connect"))
    )
    (net (code "140") (name "unconnected-(J8A-GPIO25-Pad41)") (class "Default")
      (node (ref "J8") (pin "41") (pinfunction "GPIO25_41") (pintype "passive+no_connect"))
    )
    (net (code "141") (name "unconnected-(J8A-GPIO26-Pad24)") (class "Default")
      (node (ref "J8") (pin "24") (pinfunction "GPIO26_24") (pintype "passive+no_connect"))
    )
    (net (code "142") (name "unconnected-(J8A-SD_DAT4-Pad68)") (class "Default")
      (node (ref "J8") (pin "68") (pinfunction "SD_DAT4_68") (pintype "passive+no_connect"))
    )
    (net (code "143") (name "unconnected-(J8A-SD_DAT5-Pad64)") (class "Default")
      (node (ref "J8") (pin "64") (pinfunction "SD_DAT5_64") (pintype "passive+no_connect"))
    )
    (net (code "144") (name "unconnected-(J8A-SD_DAT6-Pad72)") (class "Default")
      (node (ref "J8") (pin "72") (pinfunction "SD_DAT6_72") (pintype "passive+no_connect"))
    )
    (net (code "145") (name "unconnected-(J8A-SD_DAT7-Pad70)") (class "Default")
      (node (ref "J8") (pin "70") (pinfunction "SD_DAT7_70") (pintype "passive+no_connect"))
    )
    (net (code "146") (name "unconnected-(J8A-SD_VDD_OVERRIDE-Pad73)") (class "Default")
      (node (ref "J8") (pin "73") (pinfunction "SD_VDD_OVERRIDE_73") (pintype "passive+no_connect"))
    )
  )
)
